# schema.net
KiCad netlist of a schematic drawn in EAGLE
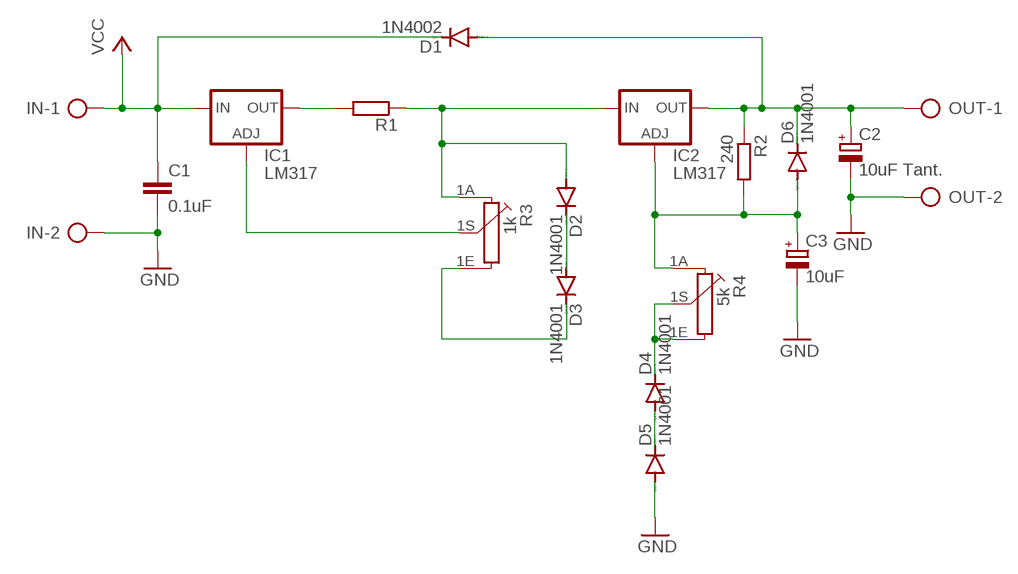
[diagram p0: schematic, sheet 1]

(export (version "E")
  (design (tool "Eeschema 10.0.6"))
  (components
    (comp (ref "C1")
      (value "0.1uF")
      (footprint "eagle-import:C025-024X044")
      (libsource (lib "eagle-import") (part "C-EU025-024X044"))
    )
    (comp (ref "C2")
      (value "10uF Tant.")
      (footprint "eagle-import:E2-5")
      (libsource (lib "eagle-import") (part "CPOL-EUE2-5"))
    )
    (comp (ref "C3")
      (value "10uF")
      (footprint "eagle-import:E2-5")
      (libsource (lib "eagle-import") (part "CPOL-EUE2-5"))
    )
    (comp (ref "D1")
      (value "1N4002")
      (footprint "eagle-import:DO41-10")
      (libsource (lib "eagle-import") (part "1N4004"))
    )
    (comp (ref "D2")
      (value "1N4001")
      (footprint "eagle-import:DO41-10")
      (libsource (lib "eagle-import") (part "1N4004"))
    )
    (comp (ref "D3")
      (value "1N4001")
      (footprint "eagle-import:DO41-10")
      (libsource (lib "eagle-import") (part "1N4004"))
    )
    (comp (ref "D4")
      (value "1N4001")
      (footprint "eagle-import:DO41-10")
      (libsource (lib "eagle-import") (part "1N4004"))
    )
    (comp (ref "D5")
      (value "1N4001")
      (footprint "eagle-import:DO41-10")
      (libsource (lib "eagle-import") (part "1N4004"))
    )
    (comp (ref "D6")
      (value "1N4001")
      (footprint "eagle-import:DO41-10")
      (libsource (lib "eagle-import") (part "1N4004"))
    )
    (comp (ref "IC1")
      (value "LM317")
      (footprint "eagle-import:317TS")
      (libsource (lib "eagle-import") (part "LM317TS"))
    )
    (comp (ref "IC2")
      (value "LM317")
      (footprint "eagle-import:317TS")
      (libsource (lib "eagle-import") (part "LM317TS"))
    )
    (comp (ref "IN")
      (value "SMKDSP_1,5/2")
      (footprint "eagle-import:SMKDSP_1,5_2")
      (fields (field (name "MF") "FARNELL") (field (name "MPN") "1733570"))
      (libsource (lib "eagle-import") (part "SMKDSP_1,5/2"))
    )
    (comp (ref "OUT")
      (value "SMKDSP_1,5/2")
      (footprint "eagle-import:SMKDSP_1,5_2")
      (fields (field (name "MF") "FARNELL") (field (name "MPN") "1733570"))
      (libsource (lib "eagle-import") (part "SMKDSP_1,5/2"))
    )
    (comp (ref "R1")
      (value "R-EU_0204/7")
      (footprint "eagle-import:0204_7")
      (libsource (lib "eagle-import") (part "R-EU_0204/7"))
    )
    (comp (ref "R2")
      (value "240")
      (footprint "eagle-import:0204_7")
      (libsource (lib "eagle-import") (part "R-EU_0204/7"))
    )
    (comp (ref "R3")
      (value "1k")
      (footprint "eagle-import:PC16S")
      (libsource (lib "eagle-import") (part "PC16S"))
    )
    (comp (ref "R4")
      (value "5k")
      (footprint "eagle-import:PC16S")
      (libsource (lib "eagle-import") (part "PC16S"))
    )
  )
  (nets
    (net (code "1") (name "GND") (class "Default")
      (node (ref "C1") (pin "2") (pinfunction "2_2") (pintype "passive"))
      (node (ref "C2") (pin "-") (pinfunction "-_-") (pintype "passive"))
      (node (ref "C3") (pin "-") (pinfunction "-_-") (pintype "passive"))
      (node (ref "D5") (pin "A") (pinfunction "A_A") (pintype "passive"))
      (node (ref "IN") (pin "2") (pinfunction "KL_2") (pintype "passive"))
      (node (ref "OUT") (pin "2") (pinfunction "KL_2") (pintype "passive"))
    )
    (net (code "2") (name "Net-(D2-PadC)") (class "Default")
      (node (ref "D2") (pin "C") (pinfunction "C_C") (pintype "passive"))
      (node (ref "D3") (pin "A") (pinfunction "A_A") (pintype "passive"))
    )
    (net (code "3") (name "Net-(D3-PadC)") (class "Default")
      (node (ref "D3") (pin "C") (pinfunction "C_C") (pintype "passive"))
      (node (ref "R3") (pin "1E") (pinfunction "1E_1E") (pintype "passive"))
    )
    (net (code "4") (name "Net-(D4-PadA)") (class "Default")
      (node (ref "D4") (pin "A") (pinfunction "A_A") (pintype "passive"))
      (node (ref "D5") (pin "C") (pinfunction "C_C") (pintype "passive"))
    )
    (net (code "5") (name "Net-(D4-PadC)") (class "Default")
      (node (ref "D4") (pin "C") (pinfunction "C_C") (pintype "passive"))
      (node (ref "R4") (pin "1E") (pinfunction "1E_1E") (pintype "passive"))
      (node (ref "R4") (pin "1S") (pinfunction "1S_1S") (pintype "passive"))
    )
    (net (code "6") (name "Net-(IC1-ADJ)") (class "Default")
      (node (ref "IC1") (pin "1") (pinfunction "ADJ_1") (pintype "input"))
      (node (ref "R3") (pin "1S") (pinfunction "1S_1S") (pintype "passive"))
    )
    (net (code "7") (name "Net-(IC1-OUT)") (class "Default")
      (node (ref "IC1") (pin "2") (pinfunction "OUT_2") (pintype "passive"))
      (node (ref "R1") (pin "2") (pinfunction "2_2") (pintype "passive"))
    )
    (net (code "8") (name "Net-(IC2-ADJ)") (class "Default")
      (node (ref "C3") (pin "+") (pinfunction "+_+") (pintype "passive"))
      (node (ref "D6") (pin "A") (pinfunction "A_A") (pintype "passive"))
      (node (ref "IC2") (pin "1") (pinfunction "ADJ_1") (pintype "input"))
      (node (ref "R2") (pin "2") (pinfunction "2_2") (pintype "passive"))
      (node (ref "R4") (pin "1A") (pinfunction "1A_1A") (pintype "passive"))
    )
    (net (code "9") (name "Net-(IC2-IN)") (class "Default")
      (node (ref "D2") (pin "A") (pinfunction "A_A") (pintype "passive"))
      (node (ref "IC2") (pin "3") (pinfunction "IN_3") (pintype "input"))
      (node (ref "R1") (pin "1") (pinfunction "1_1") (pintype "passive"))
      (node (ref "R3") (pin "1A") (pinfunction "1A_1A") (pintype "passive"))
    )
    (net (code "10") (name "Net-(IC2-OUT)") (class "Default")
      (node (ref "C2") (pin "+") (pinfunction "+_+") (pintype "passive"))
      (node (ref "D1") (pin "A") (pinfunction "A_A") (pintype "passive"))
      (node (ref "D6") (pin "C") (pinfunction "C_C") (pintype "passive"))
      (node (ref "IC2") (pin "2") (pinfunction "OUT_2") (pintype "passive"))
      (node (ref "OUT") (pin "1") (pinfunction "KL_1") (pintype "passive"))
      (node (ref "R2") (pin "1") (pinfunction "1_1") (pintype "passive"))
    )
    (net (code "11") (name "VCC") (class "Default")
      (node (ref "C1") (pin "1") (pinfunction "1_1") (pintype "passive"))
      (node (ref "D1") (pin "C") (pinfunction "C_C") (pintype "passive"))
      (node (ref "IC1") (pin "3") (pinfunction "IN_3") (pintype "input"))
      (node (ref "IN") (pin "1") (pinfunction "KL_1") (pintype "passive"))
    )
  )
)
